# usb-cereal-sch.net
KiCad netlist of a schematic drawn in Altium Designer
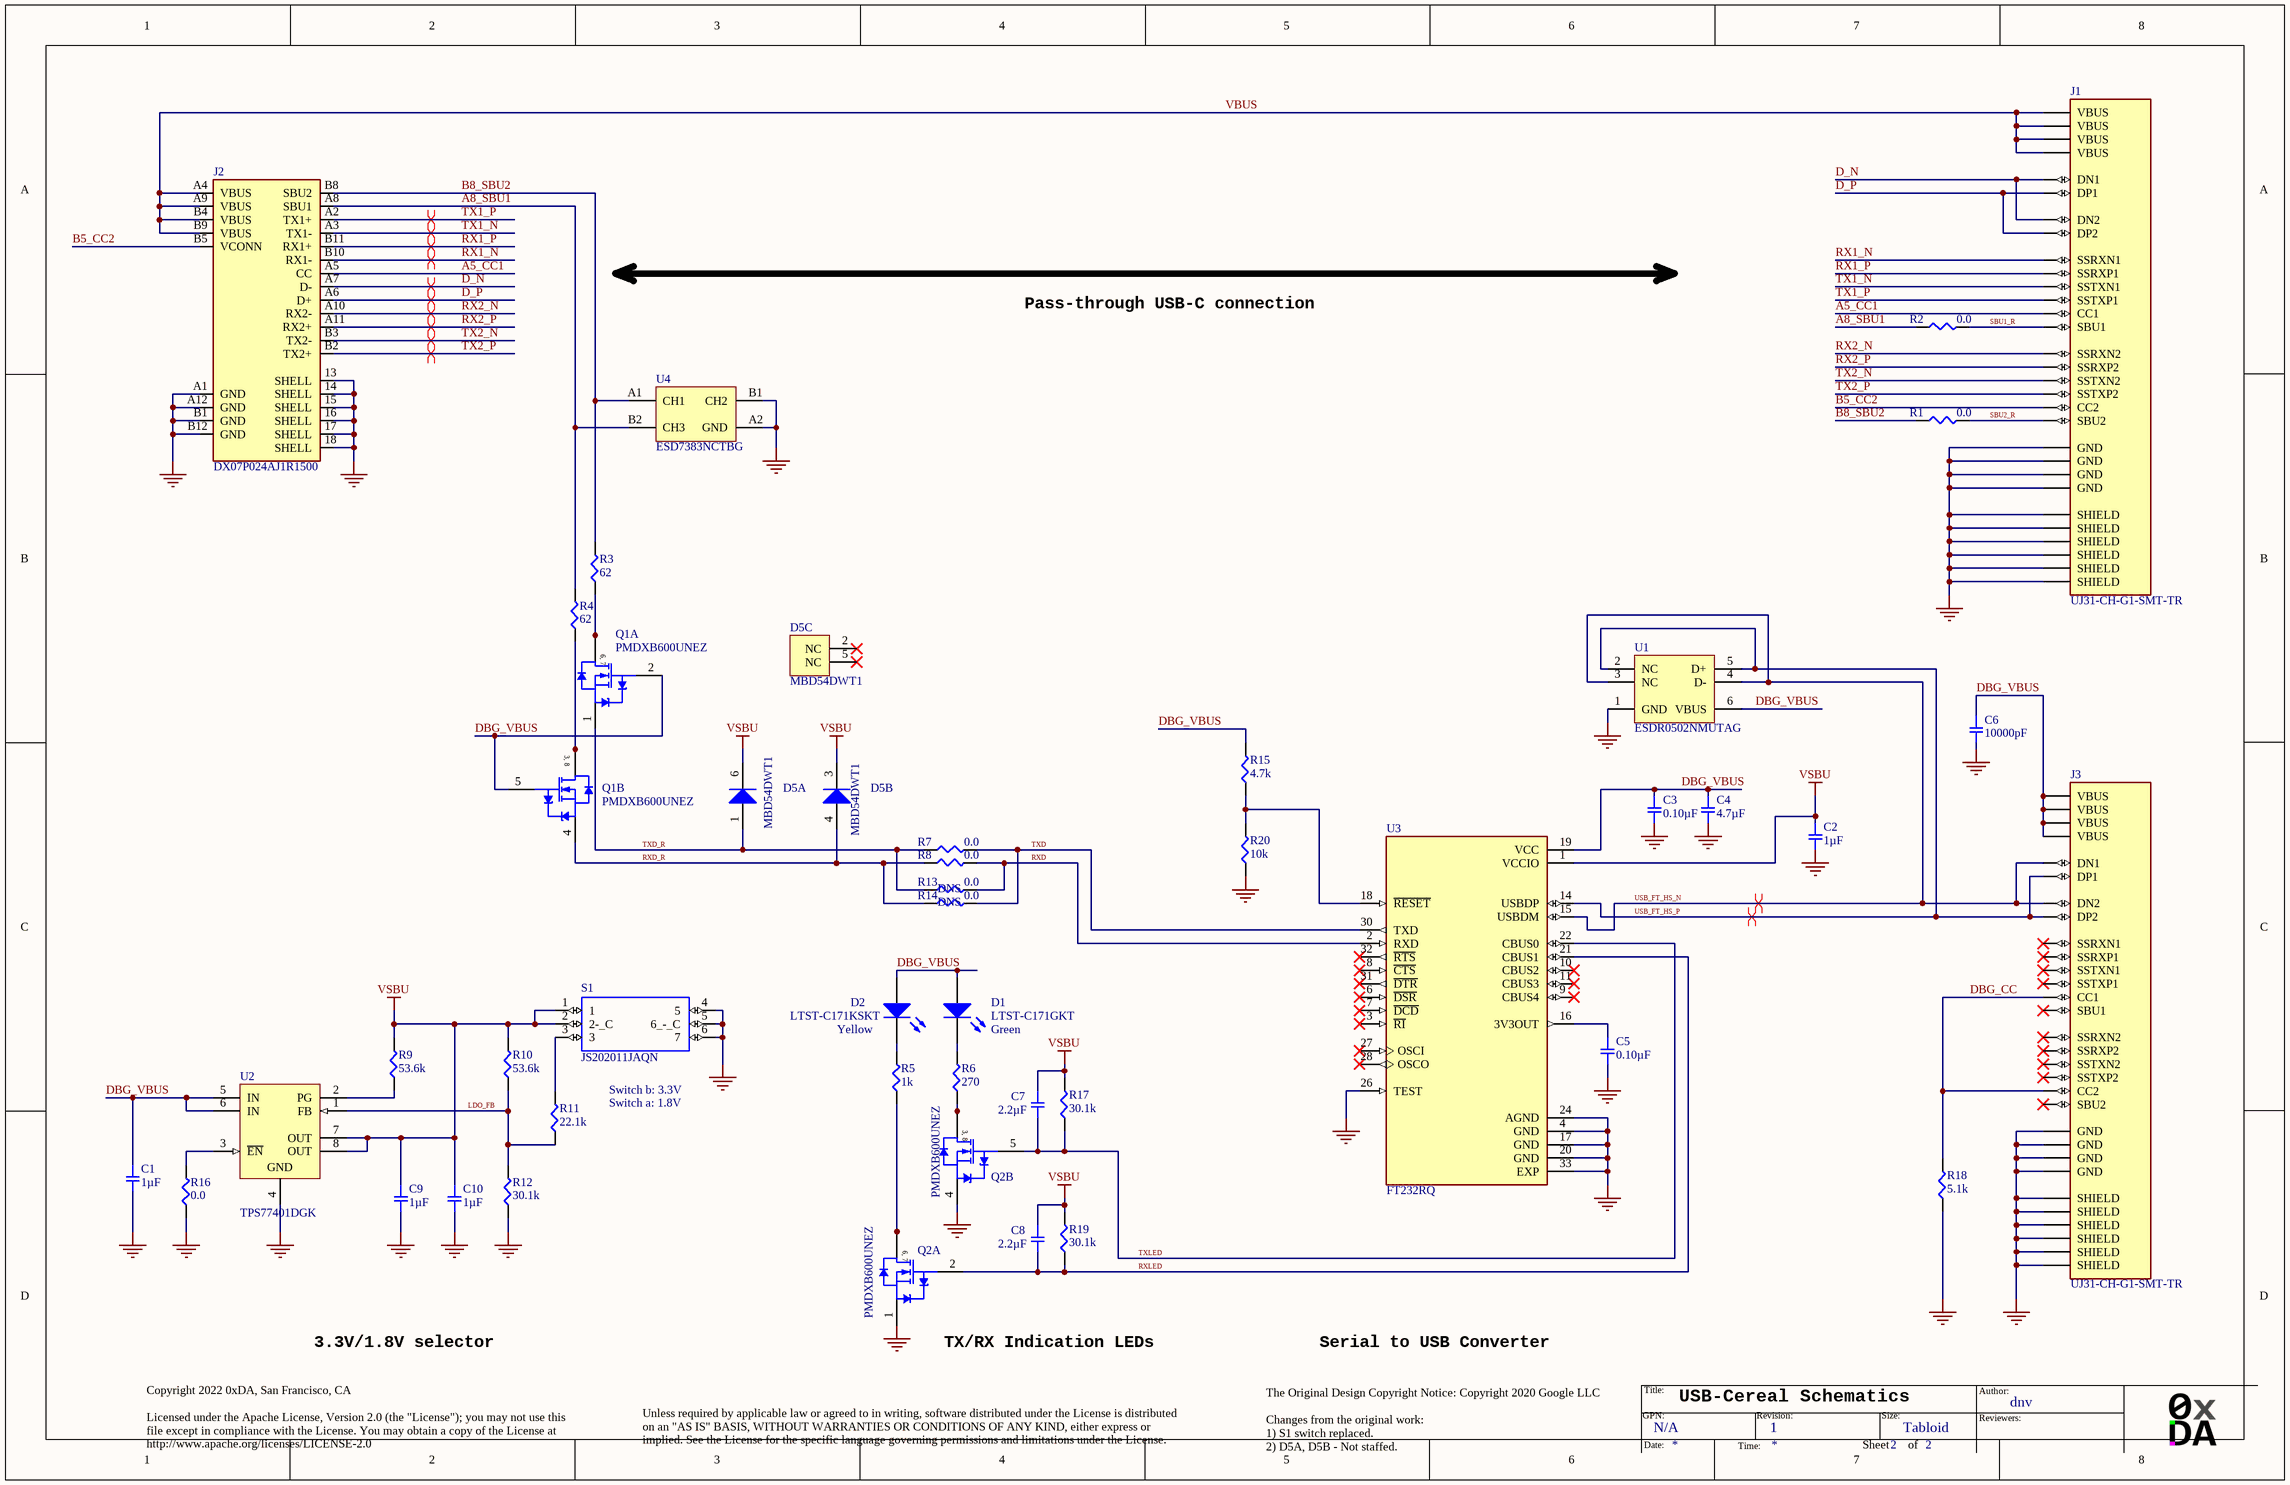
[diagram p0: usb-cereal-sch.SchDoc]

(export (version "E")
  (design (tool "Eeschema 10.0.6"))
  (components
    (comp (ref "C1")
      (value "1µF")
      (footprint "SMD-0201C")
      (description "CAP CER 1UF 6.3V X5R 0201")
      (fields
        (field (name "DIGI-KEY PART NUMBER") "490-7229-1-ND")
        (field (name "PART NUMBER") "GRM033R60J105MEA2D")
      )
      (libsource (lib "capacitor_murata_0201") (part "GRM033R60J105MEA2D"))
    )
    (comp (ref "C2")
      (value "1µF")
      (footprint "SMD-0201C")
      (description "CAP CER 1UF 6.3V X5R 0201")
      (fields
        (field (name "DIGI-KEY PART NUMBER") "490-7229-1-ND")
        (field (name "PART NUMBER") "GRM033R60J105MEA2D")
      )
      (libsource (lib "capacitor_murata_0201") (part "GRM033R60J105MEA2D"))
    )
    (comp (ref "C3")
      (value "0.10µF")
      (footprint "SMD-0201C")
      (description "CAP CER 0.1UF 10V X5R 0201")
      (fields
        (field (name "DIGI-KEY PART NUMBER") "490-5881-1-ND")
        (field (name "PART NUMBER") "GRM033R61A104KE15D")
      )
      (libsource (lib "capacitor_murata_0201") (part "GRM033R61A104KE15D"))
    )
    (comp (ref "C4")
      (value "4.7µF")
      (footprint "SMD-0201C")
      (description "CAP CER 4.7UF 6.3V X5R 0201")
      (fields
        (field (name "DIGI-KEY PART NUMBER") "490-13230-1-ND")
        (field (name "PART NUMBER") "GRM035R60J475ME15D")
      )
      (libsource (lib "cap_murata_0201") (part "GRM035R60J475ME15D"))
    )
    (comp (ref "C5")
      (value "0.10µF")
      (footprint "SMD-0201C")
      (description "CAP CER 0.1UF 10V X5R 0201")
      (fields
        (field (name "DIGI-KEY PART NUMBER") "490-5881-1-ND")
        (field (name "PART NUMBER") "GRM033R61A104KE15D")
      )
      (libsource (lib "capacitor_murata_0201") (part "GRM033R61A104KE15D"))
    )
    (comp (ref "C6")
      (value "10000pF")
      (footprint "SMD-0201C")
      (description "CAP CER 10000PF 10V X5R 0201")
      (fields
        (field (name "DIGI-KEY PART NUMBER") "490-8156-1-ND")
        (field (name "PART NUMBER") "GRM033R61A103KA01J")
      )
      (libsource (lib "capacitor_murata_0201") (part "GRM033R61A103KA01J"))
    )
    (comp (ref "C7")
      (value "2.2µF")
      (footprint "SMD-0201C")
      (description "CAP CER 2.2UF 10V X5R 0201")
      (fields
        (field (name "DIGI-KEY PART NUMBER") "490-13227-1-ND")
        (field (name "PART NUMBER") "GRM033R61A225KE47D")
      )
      (libsource (lib "cap_murata_0201") (part "GRM033R61A225KE47D"))
    )
    (comp (ref "C8")
      (value "2.2µF")
      (footprint "SMD-0201C")
      (description "CAP CER 2.2UF 10V X5R 0201")
      (fields
        (field (name "DIGI-KEY PART NUMBER") "490-13227-1-ND")
        (field (name "PART NUMBER") "GRM033R61A225KE47D")
      )
      (libsource (lib "cap_murata_0201") (part "GRM033R61A225KE47D"))
    )
    (comp (ref "C9")
      (value "1µF")
      (footprint "SMD-0201C")
      (description "CAP CER 1UF 6.3V X5R 0201")
      (fields
        (field (name "DIGI-KEY PART NUMBER") "490-7229-1-ND")
        (field (name "PART NUMBER") "GRM033R60J105MEA2D")
      )
      (libsource (lib "capacitor_murata_0201") (part "GRM033R60J105MEA2D"))
    )
    (comp (ref "C10")
      (value "1µF")
      (footprint "SMD-0201C")
      (description "CAP CER 1UF 6.3V X5R 0201")
      (fields
        (field (name "DIGI-KEY PART NUMBER") "490-7229-1-ND")
        (field (name "PART NUMBER") "GRM033R60J105MEA2D")
      )
      (libsource (lib "capacitor_murata_0201") (part "GRM033R60J105MEA2D"))
    )
    (comp (ref "D1")
      (value "LTST-C171GKT")
      (footprint "0805")
      (description "LED")
      (fields (field (name "COLOR") "Green"))
      (libsource (lib "lite-on") (part "LTST-C171GKT"))
    )
    (comp (ref "D2")
      (value "LTST-C171KSKT")
      (footprint "0805")
      (description "LED")
      (fields (field (name "COLOR") "Yellow"))
      (libsource (lib "lite-on") (part "LTST-C171KSKT"))
    )
    (comp (ref "D5")
      (value "MBD54DWT1")
      (footprint "ONSC-SOT-363-6-419B-02_W_V")
      (description "Dual Schottky Barrier Diodes, 6-Pin SOT-363, Tape and Reel")
      (fields (field (name "MANUFACTURER") "On Semiconductor"))
      (libsource (lib "diode_schottky_ON_Semi") (part "MBD54DWT1"))
    )
    (comp (ref "J1")
      (value "UJ31-CH-G1-SMT-TR")
      (footprint "SnapEDApcb:CUI_UJ31-CH-G1-SMT-TR")
      (description "Type C, USB 3.1 Gen 2, 5 A, Right Angle, Surface Mount _SMT_ , USB Receptacle")
      (fields (field (name "MF") "CUI Devices"))
      (libsource (lib "UJ31-CH-G1-SMT-TR") (part "UJ31-CH-G1-SMT-TR"))
    )
    (comp (ref "J2")
      (value "DX07P024AJ1R1500")
      (footprint "SnapEDApcb:JAE_DX07P024AJ1R1500")
      (fields (field (name "DIGI-KEY_PART_NUMBER") "670-2868-1-ND") (field (name "MF") "JAE Electronics"))
      (libsource (lib "SnapEDAsch") (part "DX07P024AJ1R1500"))
    )
    (comp (ref "J3")
      (value "UJ31-CH-G1-SMT-TR")
      (footprint "SnapEDApcb:CUI_UJ31-CH-G1-SMT-TR")
      (description "Type C, USB 3.1 Gen 2, 5 A, Right Angle, Surface Mount _SMT_ , USB Receptacle")
      (fields (field (name "MF") "CUI Devices"))
      (libsource (lib "UJ31-CH-G1-SMT-TR") (part "UJ31-CH-G1-SMT-TR"))
    )
    (comp (ref "Q1")
      (value "PMDXB600UNEZ")
      (footprint "NXP-SOT1216_N")
      (description "Dual N-Channel Trench MOSFET, 20 V, 0.6 A, -55 to 150 degC, 8-Pin SOT1216")
      (fields (field (name "MANUFACTURER") "NXP Semiconductors"))
      (libsource (lib "transistor_NXP_standard_MOSFETs") (part "PMDXB600UNEZ"))
    )
    (comp (ref "Q2")
      (value "PMDXB600UNEZ")
      (footprint "NXP-SOT1216_N")
      (description "Dual N-Channel Trench MOSFET, 20 V, 0.6 A, -55 to 150 degC, 8-Pin SOT1216")
      (fields (field (name "MANUFACTURER") "NXP Semiconductors"))
      (libsource (lib "transistor_NXP_standard_MOSFETs") (part "PMDXB600UNEZ"))
    )
    (comp (ref "R1")
      (value "0.0")
      (footprint "SMD-0201-RES")
      (description "RES SMD 0.0OHM JUMPER 1/20W 0201")
      (fields (field (name "PART NUMBER") "ERJ-1GN0R00C") (field (name "DIGI-KEY PART NUMBER") "P15979CT-ND"))
      (libsource (lib "resistor_0201_panasonic_ERJ") (part "ERJ-1GN0R00C"))
    )
    (comp (ref "R2")
      (value "0.0")
      (footprint "SMD-0201-RES")
      (description "RES SMD 0.0OHM JUMPER 1/20W 0201")
      (fields (field (name "PART NUMBER") "ERJ-1GN0R00C") (field (name "DIGI-KEY PART NUMBER") "P15979CT-ND"))
      (libsource (lib "resistor_0201_panasonic_ERJ") (part "ERJ-1GN0R00C"))
    )
    (comp (ref "R3")
      (value "62")
      (footprint "SMD-0402-RES")
      (description "RES SMD 62 OHM 5% 1/10W 0402")
      (fields (field (name "PART NUMBER") "ERJ-2GEJ620X") (field (name "DIGI-KEY PART NUMBER") "P62JCT-ND"))
      (libsource (lib "resisitor_0402_panasonic_ERJ") (part "ERJ-2GEJ620X"))
    )
    (comp (ref "R4")
      (value "62")
      (footprint "SMD-0402-RES")
      (description "RES SMD 62 OHM 5% 1/10W 0402")
      (fields (field (name "PART NUMBER") "ERJ-2GEJ620X") (field (name "DIGI-KEY PART NUMBER") "P62JCT-ND"))
      (libsource (lib "resisitor_0402_panasonic_ERJ") (part "ERJ-2GEJ620X"))
    )
    (comp (ref "R5")
      (value "1k")
      (footprint "SMD-0201-RES")
      (description "RES SMD 1K OHM 1% 1/20W 0201")
      (fields
        (field (name "PART NUMBER") "ERJ-1GEF1001C")
        (field (name "DIGI-KEY PART NUMBER") "P1.00KABCT-ND")
      )
      (libsource (lib "res_0201_panasonic_ERJ") (part "ERJ-1GEF1001C"))
    )
    (comp (ref "R6")
      (value "270")
      (footprint "SMD-0201-RES")
      (description "RES SMD 270 OHM 1% 1/20W 0201")
      (fields
        (field (name "PART NUMBER") "ERJ-1GEF2700C")
        (field (name "DIGI-KEY PART NUMBER") "P270ABCT-ND")
      )
      (libsource (lib "resistor_0201_panasonic_ERJ") (part "ERJ-1GEF2700C"))
    )
    (comp (ref "R7")
      (value "0.0")
      (footprint "SMD-0201-RES")
      (description "RES SMD 0.0OHM JUMPER 1/20W 0201")
      (fields (field (name "PART NUMBER") "ERJ-1GN0R00C") (field (name "DIGI-KEY PART NUMBER") "P15979CT-ND"))
      (libsource (lib "resistor_0201_panasonic_ERJ") (part "ERJ-1GN0R00C"))
    )
    (comp (ref "R8")
      (value "0.0")
      (footprint "SMD-0201-RES")
      (description "RES SMD 0.0OHM JUMPER 1/20W 0201")
      (fields (field (name "PART NUMBER") "ERJ-1GN0R00C") (field (name "DIGI-KEY PART NUMBER") "P15979CT-ND"))
      (libsource (lib "resistor_0201_panasonic_ERJ") (part "ERJ-1GN0R00C"))
    )
    (comp (ref "R9")
      (value "53.6k")
      (footprint "SMD-0201-RES")
      (description "RES SMD 53.6K OHM 1% 1/20W 0201")
      (fields
        (field (name "PART NUMBER") "ERJ-1GEF5362C")
        (field (name "DIGI-KEY PART NUMBER") "P53.6KABCT-ND")
      )
      (libsource (lib "resistor_0201_panasonic_ERJ") (part "ERJ-1GEF5362C"))
    )
    (comp (ref "R10")
      (value "53.6k")
      (footprint "SMD-0201-RES")
      (description "RES SMD 53.6K OHM 1% 1/20W 0201")
      (fields
        (field (name "PART NUMBER") "ERJ-1GEF5362C")
        (field (name "DIGI-KEY PART NUMBER") "P53.6KABCT-ND")
      )
      (libsource (lib "resistor_0201_panasonic_ERJ") (part "ERJ-1GEF5362C"))
    )
    (comp (ref "R11")
      (value "22.1k")
      (footprint "SMD-0201-RES")
      (description "RES SMD 22.1K OHM 1% 1/20W 0201")
      (fields
        (field (name "PART NUMBER") "ERJ-1GEF2212C")
        (field (name "DIGI-KEY PART NUMBER") "P22.1KABCT-ND")
      )
      (libsource (lib "resistor_0201_panasonic_ERJ") (part "ERJ-1GEF2212C"))
    )
    (comp (ref "R12")
      (value "30.1k")
      (footprint "SMD-0201-RES")
      (description "RES SMD 30.1K OHM 1% 1/20W 0201")
      (fields
        (field (name "PART NUMBER") "ERJ-1GEF3012C")
        (field (name "DIGI-KEY PART NUMBER") "P30.1KABCT-ND")
      )
      (libsource (lib "resistor_0201_panasonic_ERJ") (part "ERJ-1GEF3012C"))
    )
    (comp (ref "R13")
      (value "0.0")
      (footprint "SMD-0201-RES")
      (description "RES SMD 0.0OHM JUMPER 1/20W 0201")
      (fields
        (field (name "PART NUMBER") "ERJ-1GN0R00C")
        (field (name "DIGI-KEY PART NUMBER") "P15979CT-ND")
        (field (name "POPULATE") "DNS")
      )
      (libsource (lib "resistor_0201_panasonic_ERJ") (part "ERJ-1GN0R00C"))
    )
    (comp (ref "R14")
      (value "0.0")
      (footprint "SMD-0201-RES")
      (description "RES SMD 0.0OHM JUMPER 1/20W 0201")
      (fields
        (field (name "PART NUMBER") "ERJ-1GN0R00C")
        (field (name "DIGI-KEY PART NUMBER") "P15979CT-ND")
        (field (name "POPULATE") "DNS")
      )
      (libsource (lib "resistor_0201_panasonic_ERJ") (part "ERJ-1GN0R00C"))
    )
    (comp (ref "R15")
      (value "4.7k")
      (footprint "SMD-0201-RES")
      (description "RES SMD 4.7K OHM 5% 1/20W 0201")
      (fields
        (field (name "PART NUMBER") "ERJ-1GEJ472C")
        (field (name "DIGI-KEY PART NUMBER") "P4.7KAGCT-ND")
      )
      (libsource (lib "res_0201_panasonic_ERJ") (part "ERJ-1GEJ472C"))
    )
    (comp (ref "R16")
      (value "0.0")
      (footprint "SMD-0201-RES")
      (description "RES SMD 0.0OHM JUMPER 1/20W 0201")
      (fields (field (name "PART NUMBER") "ERJ-1GN0R00C") (field (name "DIGI-KEY PART NUMBER") "P15979CT-ND"))
      (libsource (lib "resistor_0201_panasonic_ERJ") (part "ERJ-1GN0R00C"))
    )
    (comp (ref "R17")
      (value "30.1k")
      (footprint "SMD-0201-RES")
      (description "RES SMD 30.1K OHM 1% 1/20W 0201")
      (fields
        (field (name "PART NUMBER") "ERJ-1GEF3012C")
        (field (name "DIGI-KEY PART NUMBER") "P30.1KABCT-ND")
      )
      (libsource (lib "resistor_0201_panasonic_ERJ") (part "ERJ-1GEF3012C"))
    )
    (comp (ref "R18")
      (value "5.1k")
      (footprint "SMD-0201-RES")
      (description "RES SMD 5.1K OHM 1% 1/20W 0201")
      (fields
        (field (name "PART NUMBER") "ERJ-1GEF5101C")
        (field (name "DIGI-KEY PART NUMBER") "P5.10KABCT-ND")
      )
      (libsource (lib "resistor_0201_panasonic_ERJ") (part "ERJ-1GEF5101C"))
    )
    (comp (ref "R19")
      (value "30.1k")
      (footprint "SMD-0201-RES")
      (description "RES SMD 30.1K OHM 1% 1/20W 0201")
      (fields
        (field (name "PART NUMBER") "ERJ-1GEF3012C")
        (field (name "DIGI-KEY PART NUMBER") "P30.1KABCT-ND")
      )
      (libsource (lib "resistor_0201_panasonic_ERJ") (part "ERJ-1GEF3012C"))
    )
    (comp (ref "R20")
      (value "10k")
      (footprint "SMD-0201-RES")
      (description "RES SMD 10K OHM 5% 1/20W 0201")
      (fields (field (name "PART NUMBER") "ERJ-1GEJ103C") (field (name "DIGI-KEY PART NUMBER") "P10KAGCT-ND"))
      (libsource (lib "res_0201_panasonic_ERJ") (part "ERJ-1GEJ103C"))
    )
    (comp (ref "S1")
      (value "JS202011JAQN")
      (footprint "JS202011JAQN")
      (description "Slide Switch DPDT Surface Mount, Right Angle")
      (fields (field (name "MF") "C&K"))
      (libsource (lib "JS202011JAQN") (part "JS202011JAQN"))
    )
    (comp (ref "U1")
      (value "ESDR0502NMUTAG")
      (footprint "ONSC-UDFN-6-517AA-01_V")
      (fields (field (name "MANUFACTURER") "On Semiconductor"))
      (libsource (lib "diode_esd_ON_Semi") (part "ESDR0502NMUTAG"))
    )
    (comp (ref "U2")
      (value "TPS77401DGK")
      (footprint "TI-DGK8_N")
      (fields (field (name "MANUFACTURER") "Texas Instruments"))
      (libsource (lib "ic_pwr_ldo_TI_single_channel_ldo_0-350mA") (part "TPS77401DGK"))
    )
    (comp (ref "U3")
      (value "FT232RQ")
      (footprint "QFN50P500X500X90-33N")
      (description "USB Bridge, USB to UART USB 2.0 UART Interface 32-QFN _5x5_")
      (fields (field (name "MF") "FTDI,") (field (name "DIGI-KEY_PART_NUMBER") "768-1008-1-ND"))
      (libsource (lib "FT232RQ") (part "FT232RQ"))
    )
    (comp (ref "U4")
      (value "ESD7383NCTBG")
      (footprint "ONSC-WLCSP-4-567CB-01")
      (description "USB-OTG 3-Line Protection, 4-Pin WLCSP, Pb-Free, Tape and Reel")
      (fields (field (name "MANUFACTURER") "On Semiconductor"))
      (libsource (lib "diode_esd_ON_Semi") (part "ESD7383NCTBG"))
    )
  )
  (nets
    (net (code "1") (name "/A5_CC1") (class "Default")
      (node (ref "J1") (pin "A5") (pinfunction "CC1_A5") (pintype "bidirectional"))
      (node (ref "J2") (pin "A5") (pinfunction "CC_A5") (pintype "bidirectional"))
    )
    (net (code "2") (name "/A8_SBU1") (class "Default")
      (node (ref "J2") (pin "A8") (pinfunction "SBU1_A8") (pintype "bidirectional"))
      (node (ref "R2") (pin "1") (pinfunction "1_1") (pintype "passive"))
      (node (ref "R4") (pin "2") (pinfunction "2_2") (pintype "passive"))
      (node (ref "U4") (pin "B2") (pinfunction "CH3_B2") (pintype "passive"))
    )
    (net (code "3") (name "/B5_CC2") (class "Default")
      (node (ref "J1") (pin "B5") (pinfunction "CC2_B5") (pintype "bidirectional"))
      (node (ref "J2") (pin "B5") (pinfunction "VCONN_B5") (pintype "power_in"))
    )
    (net (code "4") (name "/B8_SBU2") (class "Default")
      (node (ref "J2") (pin "B8") (pinfunction "SBU2_B8") (pintype "bidirectional"))
      (node (ref "R1") (pin "1") (pinfunction "1_1") (pintype "passive"))
      (node (ref "R3") (pin "2") (pinfunction "2_2") (pintype "passive"))
      (node (ref "U4") (pin "A1") (pinfunction "CH1_A1") (pintype "passive"))
    )
    (net (code "5") (name "/DBG_CC") (class "Default")
      (node (ref "J3") (pin "A5") (pinfunction "CC1_A5") (pintype "bidirectional"))
      (node (ref "J3") (pin "B5") (pinfunction "CC2_B5") (pintype "bidirectional"))
      (node (ref "R18") (pin "2") (pinfunction "2_2") (pintype "passive"))
    )
    (net (code "6") (name "/DBG_VBUS") (class "Default")
      (node (ref "C1") (pin "1") (pinfunction "1_1") (pintype "passive"))
      (node (ref "C3") (pin "1") (pinfunction "1_1") (pintype "passive"))
      (node (ref "C4") (pin "1") (pinfunction "1_1") (pintype "passive"))
      (node (ref "C6") (pin "1") (pinfunction "1_1") (pintype "passive"))
      (node (ref "D1") (pin "1") (pinfunction "A_1") (pintype "passive"))
      (node (ref "D2") (pin "1") (pinfunction "A_1") (pintype "passive"))
      (node (ref "J3") (pin "A4") (pinfunction "VBUS_A4") (pintype "power_in"))
      (node (ref "J3") (pin "A9") (pinfunction "VBUS_A9") (pintype "power_in"))
      (node (ref "J3") (pin "B4") (pinfunction "VBUS_B4") (pintype "power_in"))
      (node (ref "J3") (pin "B9") (pinfunction "VBUS_B9") (pintype "power_in"))
      (node (ref "Q1") (pin "2") (pinfunction "G1_2") (pintype "passive"))
      (node (ref "Q1") (pin "5") (pinfunction "G2_5") (pintype "passive"))
      (node (ref "R15") (pin "2") (pinfunction "2_2") (pintype "passive"))
      (node (ref "U1") (pin "6") (pinfunction "VBUS_6") (pintype "power_in"))
      (node (ref "U2") (pin "5") (pinfunction "IN_5") (pintype "power_in"))
      (node (ref "U2") (pin "6") (pinfunction "IN_6") (pintype "power_in"))
      (node (ref "U3") (pin "19") (pinfunction "VCC_19") (pintype "power_in"))
    )
    (net (code "7") (name "/D_N") (class "Default")
      (node (ref "J1") (pin "A7") (pinfunction "DN1_A7") (pintype "bidirectional"))
      (node (ref "J1") (pin "B7") (pinfunction "DN2_B7") (pintype "bidirectional"))
      (node (ref "J2") (pin "A7") (pinfunction "D-_A7") (pintype "bidirectional"))
    )
    (net (code "8") (name "/D_P") (class "Default")
      (node (ref "J1") (pin "A6") (pinfunction "DP1_A6") (pintype "bidirectional"))
      (node (ref "J1") (pin "B6") (pinfunction "DP2_B6") (pintype "bidirectional"))
      (node (ref "J2") (pin "A6") (pinfunction "D+_A6") (pintype "bidirectional"))
    )
    (net (code "9") (name "/LDO_FB") (class "Default")
      (node (ref "R10") (pin "1") (pinfunction "1_1") (pintype "passive"))
      (node (ref "R11") (pin "1") (pinfunction "1_1") (pintype "passive"))
      (node (ref "R12") (pin "2") (pinfunction "2_2") (pintype "passive"))
      (node (ref "U2") (pin "1") (pinfunction "FB_1") (pintype "input"))
    )
    (net (code "10") (name "/RX1_N") (class "Default")
      (node (ref "J1") (pin "B10") (pinfunction "SSRXN1_B10") (pintype "bidirectional"))
      (node (ref "J2") (pin "B10") (pinfunction "RX1-_B10") (pintype "bidirectional"))
    )
    (net (code "11") (name "/RX1_P") (class "Default")
      (node (ref "J1") (pin "B11") (pinfunction "SSRXP1_B11") (pintype "bidirectional"))
      (node (ref "J2") (pin "B11") (pinfunction "RX1+_B11") (pintype "bidirectional"))
    )
    (net (code "12") (name "/RX2_N") (class "Default")
      (node (ref "J1") (pin "A10") (pinfunction "SSRXN2_A10") (pintype "bidirectional"))
      (node (ref "J2") (pin "A10") (pinfunction "RX2-_A10") (pintype "bidirectional"))
    )
    (net (code "13") (name "/RX2_P") (class "Default")
      (node (ref "J1") (pin "A11") (pinfunction "SSRXP2_A11") (pintype "bidirectional"))
      (node (ref "J2") (pin "A11") (pinfunction "RX2+_A11") (pintype "bidirectional"))
    )
    (net (code "14") (name "/RXD") (class "Default")
      (node (ref "R13") (pin "2") (pinfunction "2_2") (pintype "passive"))
      (node (ref "R8") (pin "2") (pinfunction "2_2") (pintype "passive"))
      (node (ref "U3") (pin "2") (pinfunction "RXD_2") (pintype "input"))
    )
    (net (code "15") (name "/RXD_R") (class "Default")
      (node (ref "D5") (pin "4") (pinfunction "A1_4") (pintype "passive"))
      (node (ref "Q1") (pin "4") (pinfunction "S2_4") (pintype "passive"))
      (node (ref "R14") (pin "1") (pinfunction "1_1") (pintype "passive"))
      (node (ref "R8") (pin "1") (pinfunction "1_1") (pintype "passive"))
    )
    (net (code "16") (name "/RXLED") (class "Default")
      (node (ref "C8") (pin "2") (pinfunction "2_2") (pintype "passive"))
      (node (ref "Q2") (pin "2") (pinfunction "G1_2") (pintype "passive"))
      (node (ref "R19") (pin "1") (pinfunction "1_1") (pintype "passive"))
      (node (ref "U3") (pin "21") (pinfunction "CBUS1_21") (pintype "bidirectional"))
    )
    (net (code "17") (name "/SBU1_R") (class "Default")
      (node (ref "J1") (pin "A8") (pinfunction "SBU1_A8") (pintype "bidirectional"))
      (node (ref "R2") (pin "2") (pinfunction "2_2") (pintype "passive"))
    )
    (net (code "18") (name "/SBU2_R") (class "Default")
      (node (ref "J1") (pin "B8") (pinfunction "SBU2_B8") (pintype "bidirectional"))
      (node (ref "R1") (pin "2") (pinfunction "2_2") (pintype "passive"))
    )
    (net (code "19") (name "/TX1_N") (class "Default")
      (node (ref "J1") (pin "A3") (pinfunction "SSTXN1_A3") (pintype "bidirectional"))
      (node (ref "J2") (pin "A3") (pinfunction "TX1-_A3") (pintype "bidirectional"))
    )
    (net (code "20") (name "/TX1_P") (class "Default")
      (node (ref "J1") (pin "A2") (pinfunction "SSTXP1_A2") (pintype "bidirectional"))
      (node (ref "J2") (pin "A2") (pinfunction "TX1+_A2") (pintype "bidirectional"))
    )
    (net (code "21") (name "/TX2_N") (class "Default")
      (node (ref "J1") (pin "B3") (pinfunction "SSTXN2_B3") (pintype "bidirectional"))
      (node (ref "J2") (pin "B3") (pinfunction "TX2-_B3") (pintype "bidirectional"))
    )
    (net (code "22") (name "/TX2_P") (class "Default")
      (node (ref "J1") (pin "B2") (pinfunction "SSTXP2_B2") (pintype "bidirectional"))
      (node (ref "J2") (pin "B2") (pinfunction "TX2+_B2") (pintype "bidirectional"))
    )
    (net (code "23") (name "/TXD") (class "Default")
      (node (ref "R14") (pin "2") (pinfunction "2_2") (pintype "passive"))
      (node (ref "R7") (pin "2") (pinfunction "2_2") (pintype "passive"))
      (node (ref "U3") (pin "30") (pinfunction "TXD_30") (pintype "output"))
    )
    (net (code "24") (name "/TXD_R") (class "Default")
      (node (ref "D5") (pin "1") (pinfunction "A2_1") (pintype "passive"))
      (node (ref "Q1") (pin "1") (pinfunction "S1_1") (pintype "passive"))
      (node (ref "R13") (pin "1") (pinfunction "1_1") (pintype "passive"))
      (node (ref "R7") (pin "1") (pinfunction "1_1") (pintype "passive"))
    )
    (net (code "25") (name "/TXLED") (class "Default")
      (node (ref "C7") (pin "2") (pinfunction "2_2") (pintype "passive"))
      (node (ref "Q2") (pin "5") (pinfunction "G2_5") (pintype "passive"))
      (node (ref "R17") (pin "1") (pinfunction "1_1") (pintype "passive"))
      (node (ref "U3") (pin "22") (pinfunction "CBUS0_22") (pintype "bidirectional"))
    )
    (net (code "26") (name "/USB_FT_HS_N") (class "Default")
      (node (ref "J3") (pin "A7") (pinfunction "DN1_A7") (pintype "bidirectional"))
      (node (ref "J3") (pin "B7") (pinfunction "DN2_B7") (pintype "bidirectional"))
      (node (ref "U1") (pin "3") (pinfunction "NC_3") (pintype "passive"))
      (node (ref "U1") (pin "4") (pinfunction "D-_4") (pintype "passive"))
      (node (ref "U3") (pin "15") (pinfunction "USBDM_15") (pintype "bidirectional"))
    )
    (net (code "27") (name "/USB_FT_HS_P") (class "Default")
      (node (ref "J3") (pin "A6") (pinfunction "DP1_A6") (pintype "bidirectional"))
      (node (ref "J3") (pin "B6") (pinfunction "DP2_B6") (pintype "bidirectional"))
      (node (ref "U1") (pin "2") (pinfunction "NC_2") (pintype "passive"))
      (node (ref "U1") (pin "5") (pinfunction "D+_5") (pintype "passive"))
      (node (ref "U3") (pin "14") (pinfunction "USBDP_14") (pintype "bidirectional"))
    )
    (net (code "28") (name "/VBUS") (class "Default")
      (node (ref "J1") (pin "A4") (pinfunction "VBUS_A4") (pintype "power_in"))
      (node (ref "J1") (pin "A9") (pinfunction "VBUS_A9") (pintype "power_in"))
      (node (ref "J1") (pin "B4") (pinfunction "VBUS_B4") (pintype "power_in"))
      (node (ref "J1") (pin "B9") (pinfunction "VBUS_B9") (pintype "power_in"))
      (node (ref "J2") (pin "A4") (pinfunction "VBUS_A4") (pintype "power_in"))
      (node (ref "J2") (pin "A9") (pinfunction "VBUS_A9") (pintype "power_in"))
      (node (ref "J2") (pin "B4") (pinfunction "VBUS_B4") (pintype "power_in"))
      (node (ref "J2") (pin "B9") (pinfunction "VBUS_B9") (pintype "power_in"))
    )
    (net (code "29") (name "GND") (class "Default")
      (node (ref "C1") (pin "2") (pinfunction "2_2") (pintype "passive"))
      (node (ref "C10") (pin "2") (pinfunction "2_2") (pintype "passive"))
      (node (ref "C2") (pin "2") (pinfunction "2_2") (pintype "passive"))
      (node (ref "C3") (pin "2") (pinfunction "2_2") (pintype "passive"))
      (node (ref "C4") (pin "2") (pinfunction "2_2") (pintype "passive"))
      (node (ref "C5") (pin "2") (pinfunction "2_2") (pintype "passive"))
      (node (ref "C6") (pin "2") (pinfunction "2_2") (pintype "passive"))
      (node (ref "C9") (pin "2") (pinfunction "2_2") (pintype "passive"))
      (node (ref "J1") (pin "A1") (pinfunction "GND_A1") (pintype "power_in"))
      (node (ref "J1") (pin "A12") (pinfunction "GND_A12") (pintype "power_in"))
      (node (ref "J1") (pin "B1") (pinfunction "GND_B1") (pintype "power_in"))
      (node (ref "J1") (pin "B12") (pinfunction "GND_B12") (pintype "power_in"))
      (node (ref "J1") (pin "SH1") (pinfunction "SHIELD_SH1") (pintype "power_in"))
      (node (ref "J1") (pin "SH2") (pinfunction "SHIELD_SH2") (pintype "power_in"))
      (node (ref "J1") (pin "SH3") (pinfunction "SHIELD_SH3") (pintype "power_in"))
      (node (ref "J1") (pin "SH4") (pinfunction "SHIELD_SH4") (pintype "power_in"))
      (node (ref "J1") (pin "SH5") (pinfunction "SHIELD_SH5") (pintype "power_in"))
      (node (ref "J1") (pin "SH6") (pinfunction "SHIELD_SH6") (pintype "power_in"))
      (node (ref "J2") (pin "13") (pinfunction "SHELL_13") (pintype "power_in"))
      (node (ref "J2") (pin "14") (pinfunction "SHELL_14") (pintype "power_in"))
      (node (ref "J2") (pin "15") (pinfunction "SHELL_15") (pintype "power_in"))
      (node (ref "J2") (pin "16") (pinfunction "SHELL_16") (pintype "power_in"))
      (node (ref "J2") (pin "17") (pinfunction "SHELL_17") (pintype "power_in"))
      (node (ref "J2") (pin "18") (pinfunction "SHELL_18") (pintype "power_in"))
      (node (ref "J2") (pin "A1") (pinfunction "GND_A1") (pintype "power_in"))
      (node (ref "J2") (pin "A12") (pinfunction "GND_A12") (pintype "power_in"))
      (node (ref "J2") (pin "B1") (pinfunction "GND_B1") (pintype "power_in"))
      (node (ref "J2") (pin "B12") (pinfunction "GND_B12") (pintype "power_in"))
      (node (ref "J3") (pin "A1") (pinfunction "GND_A1") (pintype "power_in"))
      (node (ref "J3") (pin "A12") (pinfunction "GND_A12") (pintype "power_in"))
      (node (ref "J3") (pin "B1") (pinfunction "GND_B1") (pintype "power_in"))
      (node (ref "J3") (pin "B12") (pinfunction "GND_B12") (pintype "power_in"))
      (node (ref "J3") (pin "SH1") (pinfunction "SHIELD_SH1") (pintype "power_in"))
      (node (ref "J3") (pin "SH2") (pinfunction "SHIELD_SH2") (pintype "power_in"))
      (node (ref "J3") (pin "SH3") (pinfunction "SHIELD_SH3") (pintype "power_in"))
      (node (ref "J3") (pin "SH4") (pinfunction "SHIELD_SH4") (pintype "power_in"))
      (node (ref "J3") (pin "SH5") (pinfunction "SHIELD_SH5") (pintype "power_in"))
      (node (ref "J3") (pin "SH6") (pinfunction "SHIELD_SH6") (pintype "power_in"))
      (node (ref "Q2") (pin "1") (pinfunction "S1_1") (pintype "passive"))
      (node (ref "Q2") (pin "4") (pinfunction "S2_4") (pintype "passive"))
      (node (ref "R12") (pin "1") (pinfunction "1_1") (pintype "passive"))
      (node (ref "R16") (pin "1") (pinfunction "1_1") (pintype "passive"))
      (node (ref "R18") (pin "1") (pinfunction "1_1") (pintype "passive"))
      (node (ref "R20") (pin "1") (pinfunction "1_1") (pintype "passive"))
      (node (ref "S1") (pin "4") (pinfunction "5_4") (pintype "bidirectional"))
      (node (ref "S1") (pin "5") (pinfunction "6_-_C_5") (pintype "bidirectional"))
      (node (ref "S1") (pin "6") (pinfunction "7_6") (pintype "bidirectional"))
      (node (ref "U1") (pin "1") (pinfunction "GND_1") (pintype "power_in"))
      (node (ref "U2") (pin "4") (pinfunction "GND_4") (pintype "power_in"))
      (node (ref "U3") (pin "17") (pinfunction "GND_17") (pintype "power_in"))
      (node (ref "U3") (pin "20") (pinfunction "GND_20") (pintype "power_in"))
      (node (ref "U3") (pin "24") (pinfunction "AGND_24") (pintype "power_in"))
      (node (ref "U3") (pin "26") (pinfunction "TEST_26") (pintype "input"))
      (node (ref "U3") (pin "33") (pinfunction "EXP_33") (pintype "power_in"))
      (node (ref "U3") (pin "4") (pinfunction "GND_4") (pintype "power_in"))
      (node (ref "U4") (pin "A2") (pinfunction "GND_A2") (pintype "power_in"))
      (node (ref "U4") (pin "B1") (pinfunction "CH2_B1") (pintype "passive"))
    )
    (net (code "30") (name "Net-(D1-K)") (class "Default")
      (node (ref "D1") (pin "2") (pinfunction "K_2") (pintype "passive"))
      (node (ref "R6") (pin "2") (pinfunction "2_2") (pintype "passive"))
    )
    (net (code "31") (name "Net-(D2-K)") (class "Default")
      (node (ref "D2") (pin "2") (pinfunction "K_2") (pintype "passive"))
      (node (ref "R5") (pin "2") (pinfunction "2_2") (pintype "passive"))
    )
    (net (code "32") (name "Net-(Q1A-D1-Pad6)") (class "Default")
      (node (ref "Q1") (pin "6") (pinfunction "D1_6") (pintype "passive"))
      (node (ref "Q1") (pin "7") (pinfunction "D1_7") (pintype "passive"))
      (node (ref "R3") (pin "1") (pinfunction "1_1") (pintype "passive"))
    )
    (net (code "33") (name "Net-(Q1B-D2-Pad3)") (class "Default")
      (node (ref "Q1") (pin "3") (pinfunction "D2_3") (pintype "passive"))
      (node (ref "Q1") (pin "8") (pinfunction "D2_8") (pintype "passive"))
      (node (ref "R4") (pin "1") (pinfunction "1_1") (pintype "passive"))
    )
    (net (code "34") (name "Net-(Q2A-D1-Pad6)") (class "Default")
      (node (ref "Q2") (pin "6") (pinfunction "D1_6") (pintype "passive"))
      (node (ref "Q2") (pin "7") (pinfunction "D1_7") (pintype "passive"))
      (node (ref "R5") (pin "1") (pinfunction "1_1") (pintype "passive"))
    )
    (net (code "35") (name "Net-(Q2B-D2-Pad3)") (class "Default")
      (node (ref "Q2") (pin "3") (pinfunction "D2_3") (pintype "passive"))
      (node (ref "Q2") (pin "8") (pinfunction "D2_8") (pintype "passive"))
      (node (ref "R6") (pin "1") (pinfunction "1_1") (pintype "passive"))
    )
    (net (code "36") (name "Net-(R11-Pad2)") (class "Default")
      (node (ref "R11") (pin "2") (pinfunction "2_2") (pintype "passive"))
      (node (ref "S1") (pin "3") (pinfunction "3_3") (pintype "bidirectional"))
    )
    (net (code "37") (name "Net-(U2-PG)") (class "Default")
      (node (ref "R9") (pin "1") (pinfunction "1_1") (pintype "passive"))
      (node (ref "U2") (pin "2") (pinfunction "PG_2") (pintype "tri_state"))
    )
    (net (code "38") (name "Net-(U2-~{EN})") (class "Default")
      (node (ref "R16") (pin "2") (pinfunction "2_2") (pintype "passive"))
      (node (ref "U2") (pin "3") (pinfunction "~{EN}_3") (pintype "input"))
    )
    (net (code "39") (name "Net-(U3-3V3OUT)") (class "Default")
      (node (ref "C5") (pin "1") (pinfunction "1_1") (pintype "passive"))
      (node (ref "U3") (pin "16") (pinfunction "3V3OUT_16") (pintype "output"))
    )
    (net (code "40") (name "Net-(U3-~{RESET})") (class "Default")
      (node (ref "R15") (pin "1") (pinfunction "1_1") (pintype "passive"))
      (node (ref "R20") (pin "2") (pinfunction "2_2") (pintype "passive"))
      (node (ref "U3") (pin "18") (pinfunction "~{RESET}_18") (pintype "input"))
    )
    (net (code "41") (name "VSBU") (class "Default")
      (node (ref "C10") (pin "1") (pinfunction "1_1") (pintype "passive"))
      (node (ref "C2") (pin "1") (pinfunction "1_1") (pintype "passive"))
      (node (ref "C7") (pin "1") (pinfunction "1_1") (pintype "passive"))
      (node (ref "C8") (pin "1") (pinfunction "1_1") (pintype "passive"))
      (node (ref "C9") (pin "1") (pinfunction "1_1") (pintype "passive"))
      (node (ref "D5") (pin "3") (pinfunction "K1_3") (pintype "passive"))
      (node (ref "D5") (pin "6") (pinfunction "K2_6") (pintype "passive"))
      (node (ref "R10") (pin "2") (pinfunction "2_2") (pintype "passive"))
      (node (ref "R17") (pin "2") (pinfunction "2_2") (pintype "passive"))
      (node (ref "R19") (pin "2") (pinfunction "2_2") (pintype "passive"))
      (node (ref "R9") (pin "2") (pinfunction "2_2") (pintype "passive"))
      (node (ref "S1") (pin "1") (pinfunction "1_1") (pintype "bidirectional"))
      (node (ref "S1") (pin "2") (pinfunction "2-_C_2") (pintype "bidirectional"))
      (node (ref "U2") (pin "7") (pinfunction "OUT_7") (pintype "power_in"))
      (node (ref "U2") (pin "8") (pinfunction "OUT_8") (pintype "power_in"))
      (node (ref "U3") (pin "1") (pinfunction "VCCIO_1") (pintype "power_in"))
    )
    (net (code "42") (name "unconnected-(D5C-NC-Pad2)") (class "Default")
      (node (ref "D5") (pin "2") (pinfunction "NC_2") (pintype "passive+no_connect"))
    )
    (net (code "43") (name "unconnected-(D5C-NC-Pad5)") (class "Default")
      (node (ref "D5") (pin "5") (pinfunction "NC_5") (pintype "passive+no_connect"))
    )
    (net (code "44") (name "unconnected-(J3-SBU1-PadA8)") (class "Default")
      (node (ref "J3") (pin "A8") (pinfunction "SBU1_A8") (pintype "bidirectional+no_connect"))
    )
    (net (code "45") (name "unconnected-(J3-SBU2-PadB8)") (class "Default")
      (node (ref "J3") (pin "B8") (pinfunction "SBU2_B8") (pintype "bidirectional+no_connect"))
    )
    (net (code "46") (name "unconnected-(J3-SSRXN1-PadB10)") (class "Default")
      (node (ref "J3") (pin "B10") (pinfunction "SSRXN1_B10") (pintype "bidirectional+no_connect"))
    )
    (net (code "47") (name "unconnected-(J3-SSRXN2-PadA10)") (class "Default")
      (node (ref "J3") (pin "A10") (pinfunction "SSRXN2_A10") (pintype "bidirectional+no_connect"))
    )
    (net (code "48") (name "unconnected-(J3-SSRXP1-PadB11)") (class "Default")
      (node (ref "J3") (pin "B11") (pinfunction "SSRXP1_B11") (pintype "bidirectional+no_connect"))
    )
    (net (code "49") (name "unconnected-(J3-SSRXP2-PadA11)") (class "Default")
      (node (ref "J3") (pin "A11") (pinfunction "SSRXP2_A11") (pintype "bidirectional+no_connect"))
    )
    (net (code "50") (name "unconnected-(J3-SSTXN1-PadA3)") (class "Default")
      (node (ref "J3") (pin "A3") (pinfunction "SSTXN1_A3") (pintype "bidirectional+no_connect"))
    )
    (net (code "51") (name "unconnected-(J3-SSTXN2-PadB3)") (class "Default")
      (node (ref "J3") (pin "B3") (pinfunction "SSTXN2_B3") (pintype "bidirectional+no_connect"))
    )
    (net (code "52") (name "unconnected-(J3-SSTXP1-PadA2)") (class "Default")
      (node (ref "J3") (pin "A2") (pinfunction "SSTXP1_A2") (pintype "bidirectional+no_connect"))
    )
    (net (code "53") (name "unconnected-(J3-SSTXP2-PadB2)") (class "Default")
      (node (ref "J3") (pin "B2") (pinfunction "SSTXP2_B2") (pintype "bidirectional+no_connect"))
    )
    (net (code "54") (name "unconnected-(U3-CBUS2-Pad10)") (class "Default")
      (node (ref "U3") (pin "10") (pinfunction "CBUS2_10") (pintype "bidirectional+no_connect"))
    )
    (net (code "55") (name "unconnected-(U3-CBUS3-Pad11)") (class "Default")
      (node (ref "U3") (pin "11") (pinfunction "CBUS3_11") (pintype "bidirectional+no_connect"))
    )
    (net (code "56") (name "unconnected-(U3-CBUS4-Pad9)") (class "Default")
      (node (ref "U3") (pin "9") (pinfunction "CBUS4_9") (pintype "bidirectional+no_connect"))
    )
    (net (code "57") (name "unconnected-(U3-OSCI-Pad27)") (class "Default")
      (node (ref "U3") (pin "27") (pinfunction "OSCI_27") (pintype "input+no_connect"))
    )
    (net (code "58") (name "unconnected-(U3-OSCO-Pad28)") (class "Default")
      (node (ref "U3") (pin "28") (pinfunction "OSCO_28") (pintype "output+no_connect"))
    )
    (net (code "59") (name "unconnected-(U3-~{CTS}-Pad8)") (class "Default")
      (node (ref "U3") (pin "8") (pinfunction "~{CTS}_8") (pintype "input+no_connect"))
    )
    (net (code "60") (name "unconnected-(U3-~{DCD}-Pad7)") (class "Default")
      (node (ref "U3") (pin "7") (pinfunction "~{DCD}_7") (pintype "input+no_connect"))
    )
    (net (code "61") (name "unconnected-(U3-~{DSR}-Pad6)") (class "Default")
      (node (ref "U3") (pin "6") (pinfunction "~{DSR}_6") (pintype "input+no_connect"))
    )
    (net (code "62") (name "unconnected-(U3-~{DTR}-Pad31)") (class "Default")
      (node (ref "U3") (pin "31") (pinfunction "~{DTR}_31") (pintype "output+no_connect"))
    )
    (net (code "63") (name "unconnected-(U3-~{RI}-Pad3)") (class "Default")
      (node (ref "U3") (pin "3") (pinfunction "~{RI}_3") (pintype "input+no_connect"))
    )
    (net (code "64") (name "unconnected-(U3-~{RTS}-Pad32)") (class "Default")
      (node (ref "U3") (pin "32") (pinfunction "~{RTS}_32") (pintype "output+no_connect"))
    )
  )
)
